# Sample_and_hold.net
KiCad netlist of a schematic drawn in Altium Designer
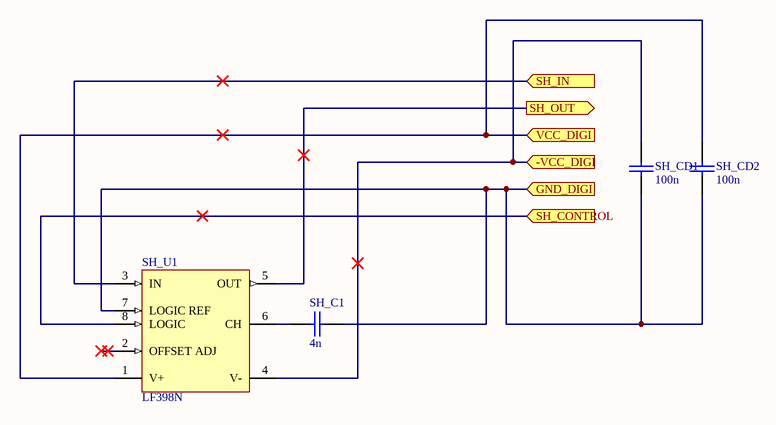
[diagram p0: Sample_and_hold.SchDoc]

(export (version "E")
  (design (tool "Eeschema 10.0.6"))
  (components
    (comp (ref "SH_C1") (value "4n") (footprint "CAP200") (libsource (lib "LIBEBAL") (part "CAP")))
    (comp (ref "SH_CD1") (value "100n") (footprint "CAP200") (libsource (lib "LIBEBAL") (part "CAP")))
    (comp (ref "SH_CD2") (value "100n") (footprint "CAP200") (libsource (lib "LIBEBAL") (part "CAP")))
    (comp (ref "SH_U1")
      (value "LF398N")
      (footprint "N08E")
      (description "Monolithic Sample and Hold Circuits, 8-pin MDIP")
      (fields (field (name "MANUFACTURER") "National Semiconductor"))
      (libsource (lib "TI_National_Semiconductor_LF398N") (part "LF398N"))
    )
  )
  (nets
    (net (code "1") (name "/-VCC_DIGI") (class "Default")
      (node (ref "SH_CD1") (pin "1") (pinfunction "1_1") (pintype "passive"))
      (node (ref "SH_U1") (pin "4") (pinfunction "V-_4") (pintype "power_in"))
    )
    (net (code "2") (name "/GND_DIGI") (class "Default")
      (node (ref "SH_C1") (pin "2") (pinfunction "2_2") (pintype "passive"))
      (node (ref "SH_CD1") (pin "2") (pinfunction "2_2") (pintype "passive"))
      (node (ref "SH_CD2") (pin "2") (pinfunction "2_2") (pintype "passive"))
      (node (ref "SH_U1") (pin "7") (pinfunction "LOGIC_REF_7") (pintype "input"))
    )
    (net (code "3") (name "/SH_CONTROL") (class "Default")
      (node (ref "SH_U1") (pin "8") (pinfunction "LOGIC_8") (pintype "input"))
    )
    (net (code "4") (name "/SH_IN") (class "Default")
      (node (ref "SH_U1") (pin "3") (pinfunction "IN_3") (pintype "input"))
    )
    (net (code "5") (name "/SH_OUT") (class "Default")
      (node (ref "SH_U1") (pin "5") (pinfunction "OUT_5") (pintype "output"))
    )
    (net (code "6") (name "/VCC_DIGI") (class "Default")
      (node (ref "SH_CD2") (pin "1") (pinfunction "1_1") (pintype "passive"))
      (node (ref "SH_U1") (pin "1") (pinfunction "V+_1") (pintype "power_in"))
    )
    (net (code "7") (name "Net-(SH_U1-CH)") (class "Default")
      (node (ref "SH_C1") (pin "1") (pinfunction "1_1") (pintype "passive"))
      (node (ref "SH_U1") (pin "6") (pinfunction "CH_6") (pintype "passive"))
    )
    (net (code "8") (name "unconnected-(SH_U1-OFFSET_ADJ-Pad2)") (class "Default")
      (node (ref "SH_U1") (pin "2") (pinfunction "OFFSET_ADJ_2") (pintype "input+no_connect"))
    )
  )
)
